# badge-pcb.net
KiCad netlist of a schematic drawn in EAGLE
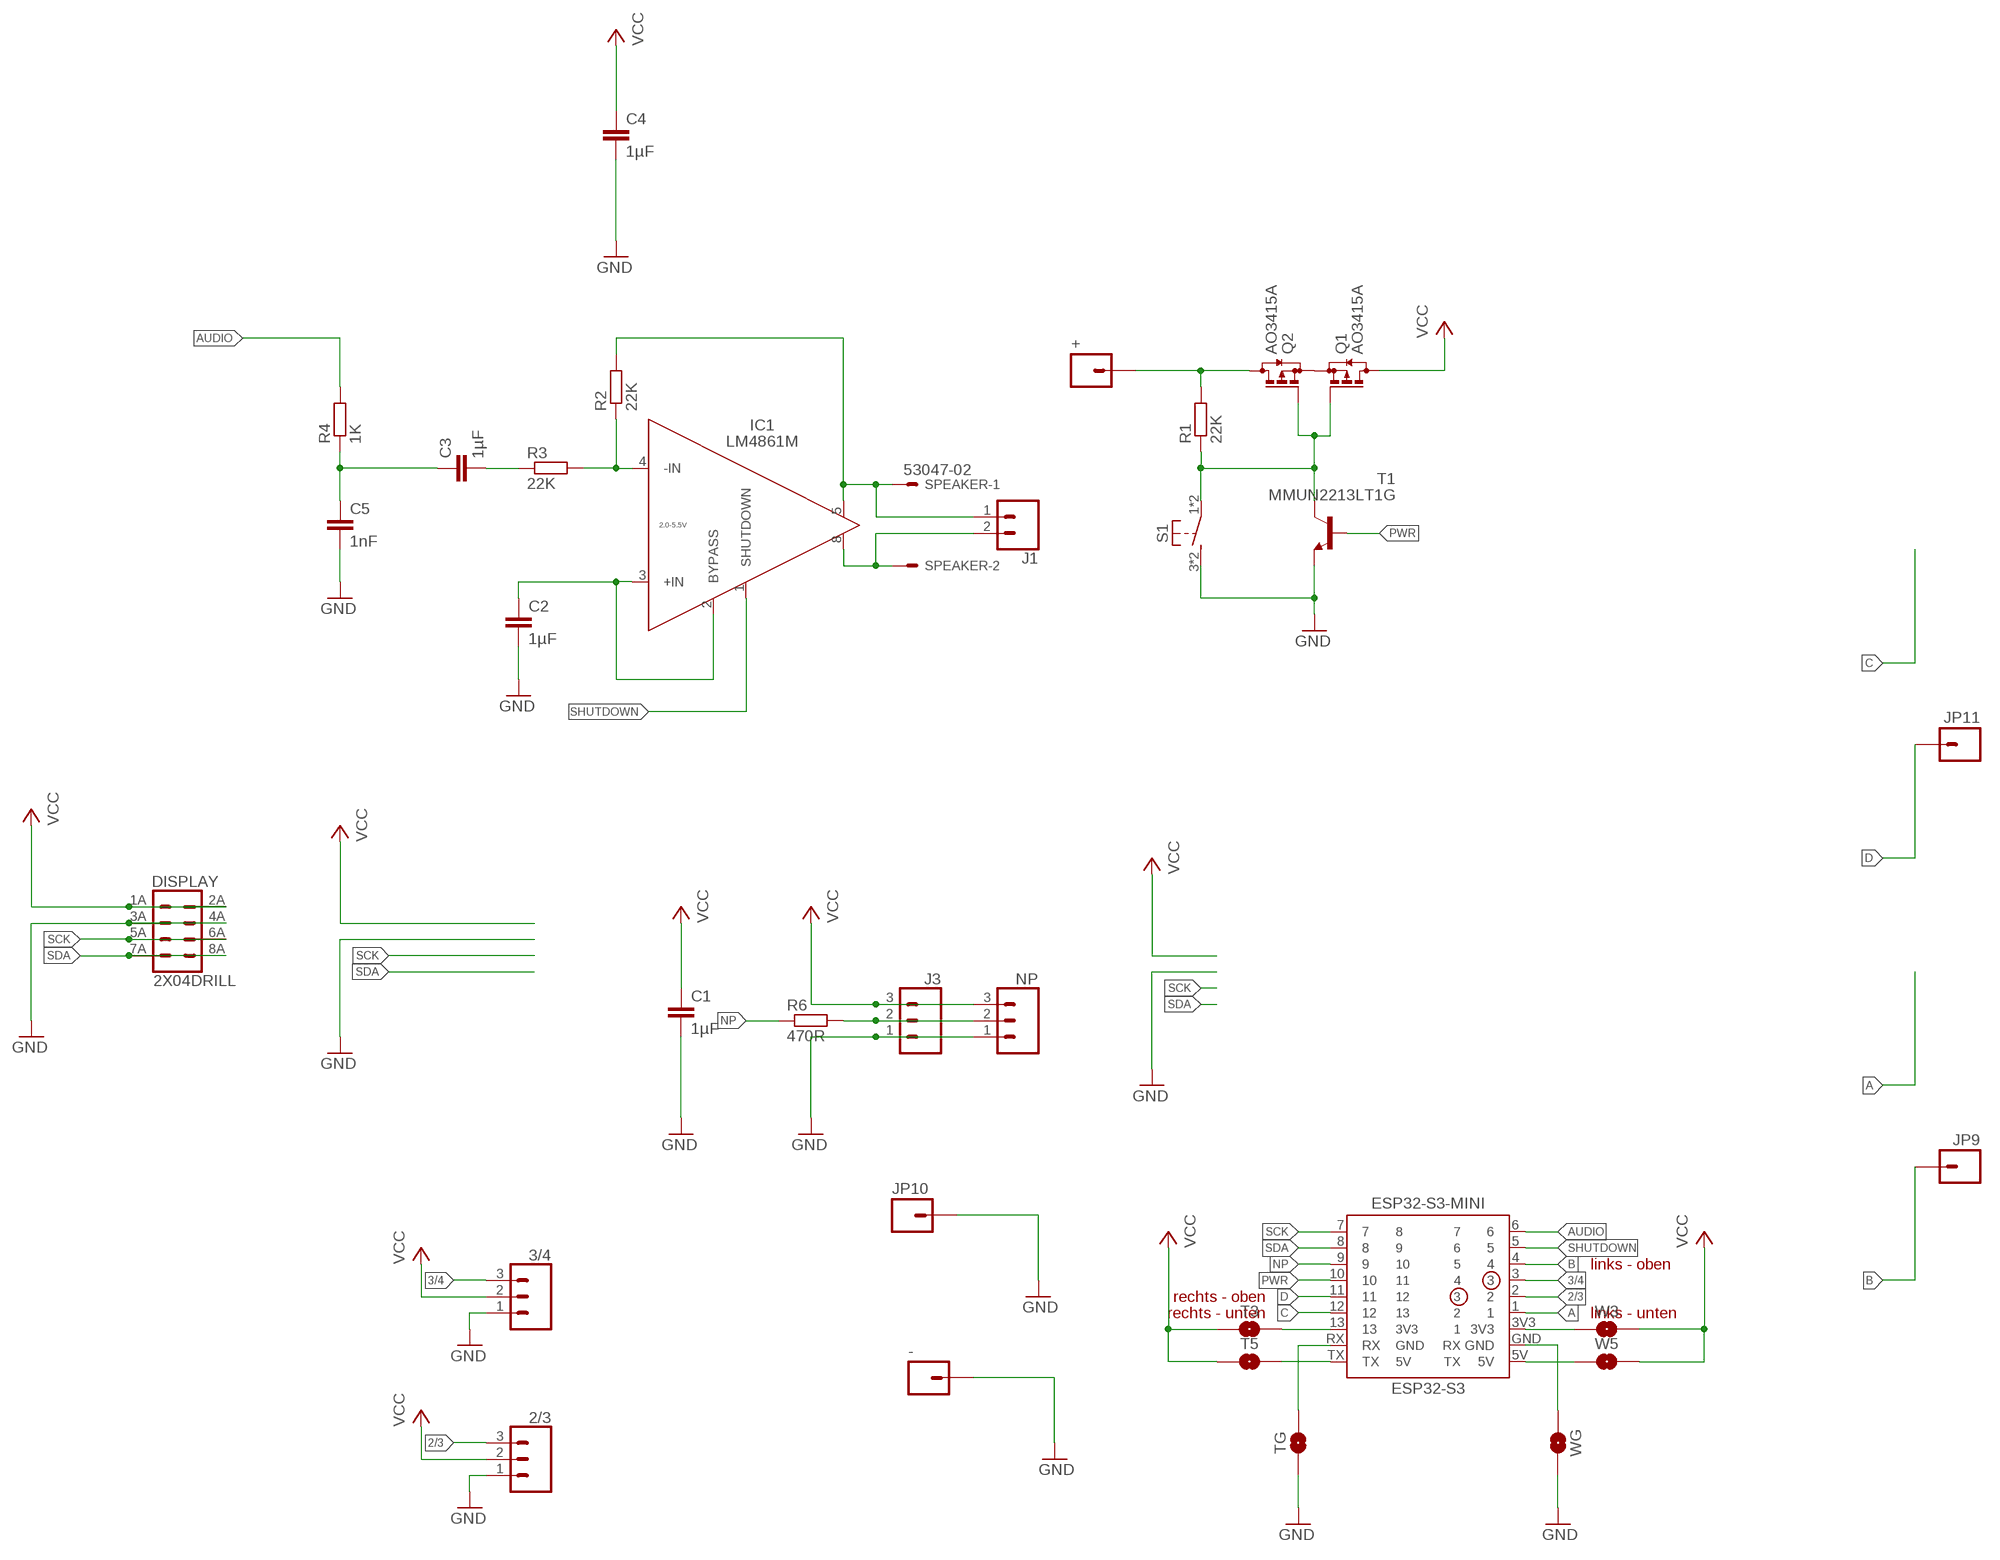
[diagram p0: schematic, sheet 1]

(export (version "E")
  (design (tool "Eeschema 10.0.6"))
  (components
    (comp (ref "+")
      (value "M01OFFSET")
      (footprint "eagle-import:1X01_OFFSET")
      (libsource (lib "eagle-import") (part "M01OFFSET"))
    )
    (comp (ref "-")
      (value "M01OFFSET")
      (footprint "eagle-import:1X01_OFFSET")
      (libsource (lib "eagle-import") (part "M01OFFSET"))
    )
    (comp (ref "2/3")
      (value "455-1750-1-ND")
      (footprint "eagle-import:1X03")
      (libsource (lib "eagle-import") (part "CONN_03"))
    )
    (comp (ref "3/4")
      (value "455-1750-1-ND")
      (footprint "eagle-import:1X03")
      (libsource (lib "eagle-import") (part "CONN_03"))
    )
    (comp (ref "C1")
      (value "1µF")
      (footprint "eagle-import:C0603K")
      (libsource (lib "eagle-import") (part "C-EUC0603K"))
    )
    (comp (ref "C2")
      (value "1µF")
      (footprint "eagle-import:C0603K")
      (libsource (lib "eagle-import") (part "C-EUC0603K"))
    )
    (comp (ref "C3")
      (value "1µF")
      (footprint "eagle-import:C0603K")
      (libsource (lib "eagle-import") (part "C-EUC0603K"))
    )
    (comp (ref "C4")
      (value "1µF")
      (footprint "eagle-import:C0603K")
      (libsource (lib "eagle-import") (part "C-EUC0603K"))
    )
    (comp (ref "C5")
      (value "1nF")
      (footprint "eagle-import:C0603K")
      (libsource (lib "eagle-import") (part "C-EUC0603K"))
    )
    (comp (ref "DISPLAY")
      (value "2X04DRILL")
      (footprint "eagle-import:2X4-DRILL")
      (libsource (lib "eagle-import") (part "2X04DRILL"))
    )
    (comp (ref "ESP32-S3")
      (value "ESP32-S3-MINI")
      (footprint "eagle-import:ESP32-S3-MINI")
      (libsource (lib "eagle-import") (part "ESP32-S3-MINI"))
    )
    (comp (ref "IC1")
      (value "LM4861M")
      (footprint "eagle-import:SOIC8")
      (libsource (lib "eagle-import") (part "LM4861M"))
    )
    (comp (ref "J1")
      (value "CONN_02")
      (footprint "eagle-import:1X02")
      (libsource (lib "eagle-import") (part "CONN_02"))
    )
    (comp (ref "J3")
      (value "455-1750-1-ND")
      (footprint "eagle-import:1X03_LONGPADS")
      (libsource (lib "eagle-import") (part "CONN_03LONGPADS"))
    )
    (comp (ref "JP9")
      (value "M01OFFSET")
      (footprint "eagle-import:1X01_OFFSET")
      (libsource (lib "eagle-import") (part "M01OFFSET"))
    )
    (comp (ref "JP10")
      (value "M01PTH")
      (footprint "eagle-import:M01_1X01")
      (libsource (lib "eagle-import") (part "M01PTH"))
    )
    (comp (ref "JP11")
      (value "M01OFFSET")
      (footprint "eagle-import:1X01_OFFSET")
      (libsource (lib "eagle-import") (part "M01OFFSET"))
    )
    (comp (ref "NP")
      (value "455-1750-1-ND")
      (footprint "eagle-import:1X03_LONGPADS")
      (libsource (lib "eagle-import") (part "CONN_03LONGPADS"))
    )
    (comp (ref "Q1")
      (value "AO3415A")
      (footprint "eagle-import:SOT23-3PIN")
      (libsource (lib "eagle-import") (part "P-CHANNEL_MOSFETIRLML2244TRPBF"))
    )
    (comp (ref "Q2")
      (value "AO3415A")
      (footprint "eagle-import:SOT23-3PIN")
      (libsource (lib "eagle-import") (part "P-CHANNEL_MOSFETIRLML2244TRPBF"))
    )
    (comp (ref "R1")
      (value "22K")
      (footprint "eagle-import:R0603")
      (libsource (lib "eagle-import") (part "R-EU_R0603"))
    )
    (comp (ref "R2")
      (value "22K")
      (footprint "eagle-import:R0603")
      (libsource (lib "eagle-import") (part "R-EU_R0603"))
    )
    (comp (ref "R3")
      (value "22K")
      (footprint "eagle-import:R0603")
      (libsource (lib "eagle-import") (part "R-EU_R0603"))
    )
    (comp (ref "R4")
      (value "1K")
      (footprint "eagle-import:R0603")
      (libsource (lib "eagle-import") (part "R-EU_R0603"))
    )
    (comp (ref "R6")
      (value "470R")
      (footprint "eagle-import:R0603")
      (libsource (lib "eagle-import") (part "R-EU_R0603"))
    )
    (comp (ref "S1")
      (value "MOMENTARY-SWITCH-SPST-21138EM")
      (footprint "eagle-import:JTP-1138EM")
      (libsource (lib "eagle-import") (part "MOMENTARY-SWITCH-SPST-21138EM"))
    )
    (comp (ref "SPEAKER")
      (value "53047-02")
      (footprint "eagle-import:53047-02")
      (fields (field (name "MF") "MOLEX") (field (name "MPN") "53047-0210"))
      (libsource (lib "eagle-import") (part "53?-02047"))
    )
    (comp (ref "T1")
      (value "MMUN2213LT1G")
      (footprint "eagle-import:SOT23")
      (libsource (lib "eagle-import") (part "BC847"))
    )
    (comp (ref "T3")
      (value "JUMPER-SMT_2_NO_SILK")
      (footprint "eagle-import:SMT-JUMPER_2_NO_SILK")
      (libsource (lib "eagle-import") (part "JUMPER-SMT_2_NO_SILK"))
    )
    (comp (ref "T5")
      (value "JUMPER-SMT_2_NO_SILK")
      (footprint "eagle-import:SMT-JUMPER_2_NO_SILK")
      (libsource (lib "eagle-import") (part "JUMPER-SMT_2_NO_SILK"))
    )
    (comp (ref "TG")
      (value "JUMPER-SMT_2_NO_SILK")
      (footprint "eagle-import:SMT-JUMPER_2_NO_SILK")
      (libsource (lib "eagle-import") (part "JUMPER-SMT_2_NO_SILK"))
    )
    (comp (ref "W3")
      (value "JUMPER-SMT_2_NO_SILK")
      (footprint "eagle-import:SMT-JUMPER_2_NO_SILK")
      (libsource (lib "eagle-import") (part "JUMPER-SMT_2_NO_SILK"))
    )
    (comp (ref "W5")
      (value "JUMPER-SMT_2_NO_SILK")
      (footprint "eagle-import:SMT-JUMPER_2_NO_SILK")
      (libsource (lib "eagle-import") (part "JUMPER-SMT_2_NO_SILK"))
    )
    (comp (ref "WG")
      (value "JUMPER-SMT_2_NO_SILK")
      (footprint "eagle-import:SMT-JUMPER_2_NO_SILK")
      (libsource (lib "eagle-import") (part "JUMPER-SMT_2_NO_SILK"))
    )
  )
  (nets
    (net (code "1") (name "2{slash}3") (class "Default")
      (node (ref "2/3") (pin "3") (pinfunction "3_3") (pintype "passive"))
      (node (ref "ESP32-S3") (pin "2") (pinfunction "2_2") (pintype "bidirectional"))
    )
    (net (code "2") (name "3{slash}4") (class "Default")
      (node (ref "3/4") (pin "3") (pinfunction "3_3") (pintype "passive"))
      (node (ref "ESP32-S3") (pin "3") (pinfunction "3_3") (pintype "bidirectional"))
    )
    (net (code "3") (name "A") (class "Default")
      (node (ref "ESP32-S3") (pin "1") (pinfunction "1_1") (pintype "bidirectional"))
    )
    (net (code "4") (name "AUDIO") (class "Default")
      (node (ref "ESP32-S3") (pin "6") (pinfunction "6_6") (pintype "bidirectional"))
      (node (ref "R4") (pin "2") (pinfunction "2_2") (pintype "passive"))
    )
    (net (code "5") (name "B") (class "Default")
      (node (ref "ESP32-S3") (pin "4") (pinfunction "4_4") (pintype "bidirectional"))
      (node (ref "JP9") (pin "1") (pinfunction "1_1") (pintype "passive"))
    )
    (net (code "6") (name "C") (class "Default")
      (node (ref "ESP32-S3") (pin "12") (pinfunction "12_12") (pintype "bidirectional"))
    )
    (net (code "7") (name "D") (class "Default")
      (node (ref "ESP32-S3") (pin "11") (pinfunction "11_11") (pintype "bidirectional"))
      (node (ref "JP11") (pin "1") (pinfunction "1_1") (pintype "passive"))
    )
    (net (code "8") (name "GND") (class "Default")
      (node (ref "-") (pin "1") (pinfunction "1_1") (pintype "passive"))
      (node (ref "2/3") (pin "1") (pinfunction "1_1") (pintype "passive"))
      (node (ref "3/4") (pin "1") (pinfunction "1_1") (pintype "passive"))
      (node (ref "C1") (pin "2") (pinfunction "2_2") (pintype "passive"))
      (node (ref "C2") (pin "2") (pinfunction "2_2") (pintype "passive"))
      (node (ref "C4") (pin "2") (pinfunction "2_2") (pintype "passive"))
      (node (ref "C5") (pin "2") (pinfunction "2_2") (pintype "passive"))
      (node (ref "DISPLAY") (pin "3A") (pinfunction "3_3A") (pintype "passive"))
      (node (ref "DISPLAY") (pin "4A") (pinfunction "4_4A") (pintype "passive"))
      (node (ref "J3") (pin "1") (pinfunction "1_1") (pintype "passive"))
      (node (ref "JP10") (pin "1") (pinfunction "1_1") (pintype "passive"))
      (node (ref "NP") (pin "1") (pinfunction "1_1") (pintype "passive"))
      (node (ref "S1") (pin "3") (pinfunction "3_3") (pintype "passive"))
      (node (ref "S1") (pin "4") (pinfunction "3_4") (pintype "passive"))
      (node (ref "T1") (pin "2") (pinfunction "E_2") (pintype "passive"))
      (node (ref "TG") (pin "1") (pinfunction "1_1") (pintype "passive"))
      (node (ref "WG") (pin "1") (pinfunction "1_1") (pintype "passive"))
    )
    (net (code "9") (name "NP") (class "Default")
      (node (ref "ESP32-S3") (pin "9") (pinfunction "9_9") (pintype "bidirectional"))
      (node (ref "R6") (pin "1") (pinfunction "1_1") (pintype "passive"))
    )
    (net (code "10") (name "Net-(C3-Pad1)") (class "Default")
      (node (ref "C3") (pin "1") (pinfunction "1_1") (pintype "passive"))
      (node (ref "C5") (pin "1") (pinfunction "1_1") (pintype "passive"))
      (node (ref "R4") (pin "1") (pinfunction "1_1") (pintype "passive"))
    )
    (net (code "11") (name "Net-(C3-Pad2)") (class "Default")
      (node (ref "C3") (pin "2") (pinfunction "2_2") (pintype "passive"))
      (node (ref "R3") (pin "1") (pinfunction "1_1") (pintype "passive"))
    )
    (net (code "12") (name "Net-(ESP32-S3-Pad3V3)") (class "Default")
      (node (ref "ESP32-S3") (pin "3V3") (pinfunction "3V3_3V3") (pintype "power_in"))
      (node (ref "W3") (pin "2") (pinfunction "2_2") (pintype "passive"))
    )
    (net (code "13") (name "Net-(ESP32-S3-Pad5V)") (class "Default")
      (node (ref "ESP32-S3") (pin "5V") (pinfunction "5V_5V") (pintype "power_in"))
      (node (ref "W5") (pin "2") (pinfunction "2_2") (pintype "passive"))
    )
    (net (code "14") (name "Net-(ESP32-S3-Pad13)") (class "Default")
      (node (ref "ESP32-S3") (pin "13") (pinfunction "13_13") (pintype "bidirectional"))
      (node (ref "T3") (pin "2") (pinfunction "2_2") (pintype "passive"))
    )
    (net (code "15") (name "Net-(ESP32-S3-PadGND)") (class "Default")
      (node (ref "ESP32-S3") (pin "GND") (pinfunction "GND_GND") (pintype "power_in"))
      (node (ref "WG") (pin "2") (pinfunction "2_2") (pintype "passive"))
    )
    (net (code "16") (name "Net-(ESP32-S3-PadRX)") (class "Default")
      (node (ref "ESP32-S3") (pin "RX") (pinfunction "RX_RX") (pintype "bidirectional"))
      (node (ref "TG") (pin "2") (pinfunction "2_2") (pintype "passive"))
    )
    (net (code "17") (name "Net-(ESP32-S3-PadTX)") (class "Default")
      (node (ref "ESP32-S3") (pin "TX") (pinfunction "TX_TX") (pintype "bidirectional"))
      (node (ref "T5") (pin "1") (pinfunction "1_1") (pintype "passive"))
    )
    (net (code "18") (name "Net-(IC1B-+IN)") (class "Default")
      (node (ref "C2") (pin "1") (pinfunction "1_1") (pintype "passive"))
      (node (ref "IC1") (pin "2") (pinfunction "BYPASS_2") (pintype "bidirectional"))
      (node (ref "IC1") (pin "3") (pinfunction "+IN_3") (pintype "input"))
    )
    (net (code "19") (name "Net-(IC1B--IN)") (class "Default")
      (node (ref "IC1") (pin "4") (pinfunction "-IN_4") (pintype "input"))
      (node (ref "R2") (pin "1") (pinfunction "1_1") (pintype "passive"))
      (node (ref "R3") (pin "2") (pinfunction "2_2") (pintype "passive"))
    )
    (net (code "20") (name "Net-(IC1B-VO1)") (class "Default")
      (node (ref "IC1") (pin "5") (pinfunction "VO1_5") (pintype "output"))
      (node (ref "J1") (pin "1") (pinfunction "1_1") (pintype "passive"))
      (node (ref "R2") (pin "2") (pinfunction "2_2") (pintype "passive"))
      (node (ref "SPEAKER") (pin "1") (pinfunction "S_1") (pintype "passive"))
    )
    (net (code "21") (name "Net-(IC1B-VO2)") (class "Default")
      (node (ref "IC1") (pin "8") (pinfunction "VO2_8") (pintype "output"))
      (node (ref "J1") (pin "2") (pinfunction "2_2") (pintype "passive"))
      (node (ref "SPEAKER") (pin "2") (pinfunction "S_2") (pintype "passive"))
    )
    (net (code "22") (name "Net-(J3-Pad2)") (class "Default")
      (node (ref "J3") (pin "2") (pinfunction "2_2") (pintype "passive"))
      (node (ref "NP") (pin "2") (pinfunction "2_2") (pintype "passive"))
      (node (ref "R6") (pin "2") (pinfunction "2_2") (pintype "passive"))
    )
    (net (code "23") (name "Net-(Q1-G)") (class "Default")
      (node (ref "Q1") (pin "1") (pinfunction "G_1") (pintype "passive"))
      (node (ref "Q2") (pin "1") (pinfunction "G_1") (pintype "passive"))
      (node (ref "R1") (pin "1") (pinfunction "1_1") (pintype "passive"))
      (node (ref "S1") (pin "1") (pinfunction "1_1") (pintype "passive"))
      (node (ref "S1") (pin "2") (pinfunction "1_2") (pintype "passive"))
      (node (ref "T1") (pin "3") (pinfunction "C_3") (pintype "passive"))
    )
    (net (code "24") (name "Net-(Q1-S)") (class "Default")
      (node (ref "Q1") (pin "2") (pinfunction "S_2") (pintype "passive"))
      (node (ref "Q2") (pin "2") (pinfunction "S_2") (pintype "passive"))
    )
    (net (code "25") (name "Net-(Q2-D)") (class "Default")
      (node (ref "+") (pin "1") (pinfunction "1_1") (pintype "passive"))
      (node (ref "Q2") (pin "3") (pinfunction "D_3") (pintype "passive"))
      (node (ref "R1") (pin "2") (pinfunction "2_2") (pintype "passive"))
    )
    (net (code "26") (name "PWR") (class "Default")
      (node (ref "ESP32-S3") (pin "10") (pinfunction "10_10") (pintype "bidirectional"))
      (node (ref "T1") (pin "1") (pinfunction "B_1") (pintype "passive"))
    )
    (net (code "27") (name "SCK") (class "Default")
      (node (ref "DISPLAY") (pin "5A") (pinfunction "5_5A") (pintype "passive"))
      (node (ref "DISPLAY") (pin "6A") (pinfunction "6_6A") (pintype "passive"))
      (node (ref "ESP32-S3") (pin "7") (pinfunction "7_7") (pintype "bidirectional"))
    )
    (net (code "28") (name "SDA") (class "Default")
      (node (ref "DISPLAY") (pin "7A") (pinfunction "7_7A") (pintype "passive"))
      (node (ref "DISPLAY") (pin "8A") (pinfunction "8_8A") (pintype "passive"))
      (node (ref "ESP32-S3") (pin "8") (pinfunction "8_8") (pintype "bidirectional"))
    )
    (net (code "29") (name "SHUTDOWN") (class "Default")
      (node (ref "ESP32-S3") (pin "5") (pinfunction "5_5") (pintype "bidirectional"))
      (node (ref "IC1") (pin "1") (pinfunction "SHUTDOWN_1") (pintype "power_in"))
    )
    (net (code "30") (name "VCC") (class "Default")
      (node (ref "2/3") (pin "2") (pinfunction "2_2") (pintype "passive"))
      (node (ref "3/4") (pin "2") (pinfunction "2_2") (pintype "passive"))
      (node (ref "C1") (pin "1") (pinfunction "1_1") (pintype "passive"))
      (node (ref "C4") (pin "1") (pinfunction "1_1") (pintype "passive"))
      (node (ref "DISPLAY") (pin "1A") (pinfunction "1_1A") (pintype "passive"))
      (node (ref "DISPLAY") (pin "2A") (pinfunction "2_2A") (pintype "passive"))
      (node (ref "J3") (pin "3") (pinfunction "3_3") (pintype "passive"))
      (node (ref "NP") (pin "3") (pinfunction "3_3") (pintype "passive"))
      (node (ref "Q1") (pin "3") (pinfunction "D_3") (pintype "passive"))
      (node (ref "T3") (pin "1") (pinfunction "1_1") (pintype "passive"))
      (node (ref "T5") (pin "2") (pinfunction "2_2") (pintype "passive"))
      (node (ref "W3") (pin "1") (pinfunction "1_1") (pintype "passive"))
      (node (ref "W5") (pin "1") (pinfunction "1_1") (pintype "passive"))
    )
  )
)
